# Ref-Board-1_5-WA-r1_0.net
KiCad netlist of a schematic drawn in Altium Designer
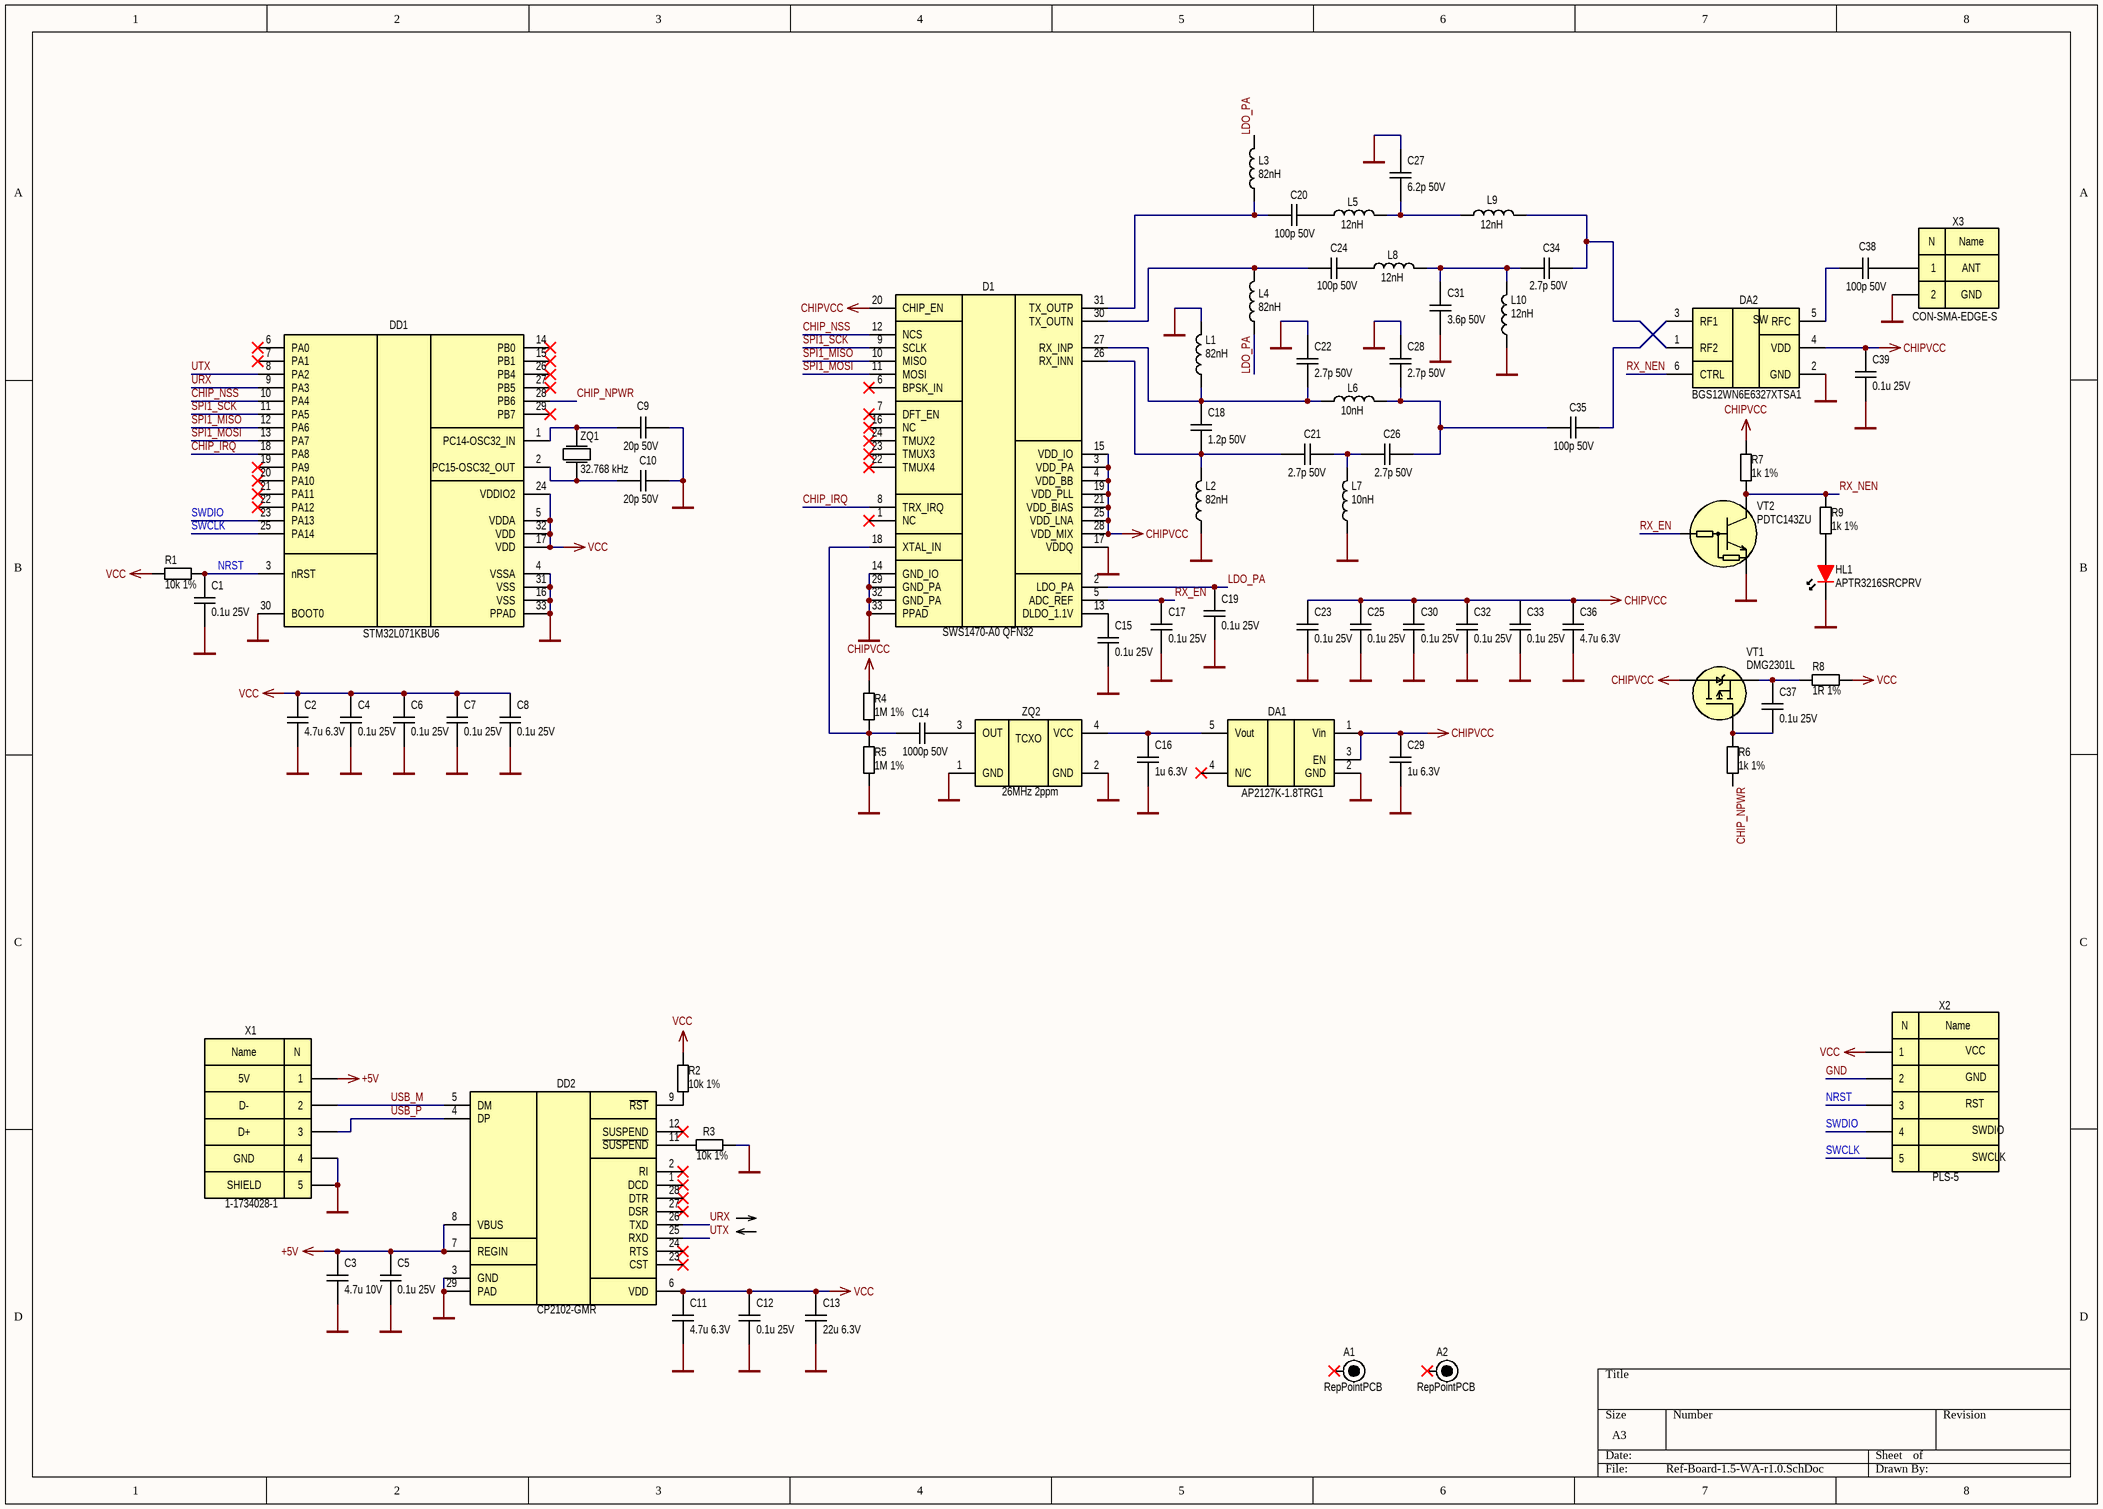
[diagram p0: Ref-Board-1.5-WA-r1.0.SchDoc]

(export (version "E")
  (design (tool "Eeschema 10.0.6"))
  (components
    (comp (ref "A1")
      (value "RepPointPCB")
      (footprint "REPzn")
      (description "Repere point d=0.5mm, D=1mm")
      (libsource (lib "Special") (part "RepPointCircD1.0"))
    )
    (comp (ref "A2")
      (value "RepPointPCB")
      (footprint "REPzn")
      (description "Repere point d=0.5mm, D=1mm")
      (libsource (lib "Special") (part "RepPointCircD1.0"))
    )
    (comp (ref "C1")
      (value "0.1u 25V")
      (footprint "C0402")
      (description "CAP CER 0.1UF 25V X7R 0402")
      (fields (field (name "PARTNUMBER") "CC0402KRX7R8BB104"))
      (libsource (lib "Capacitors") (part "CC0402KRX7R8BB104"))
    )
    (comp (ref "C2")
      (value "4.7u 6.3V")
      (footprint "C0402")
      (description "CAP CER 4.7UF 6.3V X5R 0402")
      (fields (field (name "PARTNUMBER") "CC0402KRX5R5BB475"))
      (libsource (lib "Capacitors") (part "CC0402KRX5R5BB475"))
    )
    (comp (ref "C3")
      (value "4.7u 10V")
      (footprint "C0603")
      (description "CERCAP 4.7/10V 0603 KX5R")
      (fields (field (name "PARTNUMBER") "CC0603KRX5R6BB475"))
      (libsource (lib "Capacitors") (part "CC0603KRX5R6BB475"))
    )
    (comp (ref "C4")
      (value "0.1u 25V")
      (footprint "C0402")
      (description "CAP CER 0.1UF 25V X7R 0402")
      (fields (field (name "PARTNUMBER") "CC0402KRX7R8BB104"))
      (libsource (lib "Capacitors") (part "CC0402KRX7R8BB104"))
    )
    (comp (ref "C5")
      (value "0.1u 25V")
      (footprint "C0402")
      (description "CAP CER 0.1UF 25V X7R 0402")
      (fields (field (name "PARTNUMBER") "CC0402KRX7R8BB104"))
      (libsource (lib "Capacitors") (part "CC0402KRX7R8BB104"))
    )
    (comp (ref "C6")
      (value "0.1u 25V")
      (footprint "C0402")
      (description "CAP CER 0.1UF 25V X7R 0402")
      (fields (field (name "PARTNUMBER") "CC0402KRX7R8BB104"))
      (libsource (lib "Capacitors") (part "CC0402KRX7R8BB104"))
    )
    (comp (ref "C7")
      (value "0.1u 25V")
      (footprint "C0402")
      (description "CAP CER 0.1UF 25V X7R 0402")
      (fields (field (name "PARTNUMBER") "CC0402KRX7R8BB104"))
      (libsource (lib "Capacitors") (part "CC0402KRX7R8BB104"))
    )
    (comp (ref "C8")
      (value "0.1u 25V")
      (footprint "C0402")
      (description "CAP CER 0.1UF 25V X7R 0402")
      (fields (field (name "PARTNUMBER") "CC0402KRX7R8BB104"))
      (libsource (lib "Capacitors") (part "CC0402KRX7R8BB104"))
    )
    (comp (ref "C9")
      (value "20p 50V")
      (footprint "C0402")
      (description "CAP CER 20PF 50V C0G/NPO 0402")
      (fields (field (name "PARTNUMBER") "CC0402JRNPO9BN200"))
      (libsource (lib "Capacitors") (part "CC0402JRNPO9BN200"))
    )
    (comp (ref "C10")
      (value "20p 50V")
      (footprint "C0402")
      (description "CAP CER 20PF 50V C0G/NPO 0402")
      (fields (field (name "PARTNUMBER") "CC0402JRNPO9BN200"))
      (libsource (lib "Capacitors") (part "CC0402JRNPO9BN200"))
    )
    (comp (ref "C11")
      (value "4.7u 6.3V")
      (footprint "C0402")
      (description "CAP CER 4.7UF 6.3V X5R 0402")
      (fields (field (name "PARTNUMBER") "CC0402KRX5R5BB475"))
      (libsource (lib "Capacitors") (part "CC0402KRX5R5BB475"))
    )
    (comp (ref "C12")
      (value "0.1u 25V")
      (footprint "C0402")
      (description "CAP CER 0.1UF 25V X7R 0402")
      (fields (field (name "PARTNUMBER") "CC0402KRX7R8BB104"))
      (libsource (lib "Capacitors") (part "CC0402KRX7R8BB104"))
    )
    (comp (ref "C13")
      (value "22u 6.3V")
      (footprint "C0603")
      (description "CAP CER 22UF 6.3V X5R 0603")
      (fields (field (name "PARTNUMBER") "GRM188R60J226MEA0J"))
      (libsource (lib "Capacitors") (part "GRM188R60J226MEA0J"))
    )
    (comp (ref "C14")
      (value "1000p 50V")
      (footprint "C0402")
      (description "CAP CER 1000PF 50V X7R 0402")
      (fields (field (name "PARTNUMBER") "CC0402JRX7R9BB102"))
      (libsource (lib "Capacitors") (part "CC0402JRX7R9BB102"))
    )
    (comp (ref "C15")
      (value "0.1u 25V")
      (footprint "C0402")
      (description "CAP CER 0.1UF 25V X7R 0402")
      (fields (field (name "PARTNUMBER") "CC0402KRX7R8BB104"))
      (libsource (lib "Capacitors") (part "CC0402KRX7R8BB104"))
    )
    (comp (ref "C16")
      (value "1u 6.3V")
      (footprint "C0402")
      (description "CAP CER 1UF 6.3V X5R 0402")
      (fields (field (name "PARTNUMBER") "CC0402KRX5R5BB105"))
      (libsource (lib "Capacitors") (part "CC0402KRX5R5BB105"))
    )
    (comp (ref "C17")
      (value "0.1u 25V")
      (footprint "C0402")
      (description "CAP CER 0.1UF 25V X7R 0402")
      (fields (field (name "PARTNUMBER") "CC0402KRX7R8BB104"))
      (libsource (lib "Capacitors") (part "CC0402KRX7R8BB104"))
    )
    (comp (ref "C18")
      (value "1.2p 50V")
      (footprint "C0402")
      (description "CAP CER 1.2PF 50V C0G/NPO 0402")
      (fields (field (name "PARTNUMBER") "CC0402BRNPO9BN1R2"))
      (libsource (lib "Capacitors") (part "CC0402BRNPO9BN1R2"))
    )
    (comp (ref "C19")
      (value "0.1u 25V")
      (footprint "C0402")
      (description "CAP CER 0.1UF 25V X7R 0402")
      (fields (field (name "PARTNUMBER") "CC0402KRX7R8BB104"))
      (libsource (lib "Capacitors") (part "CC0402KRX7R8BB104"))
    )
    (comp (ref "C20")
      (value "100p 50V")
      (footprint "C0402")
      (description "CAP CER 100PF 50V C0G/NPO 0402")
      (fields (field (name "PARTNUMBER") "CC0402JRNPO9BN101"))
      (libsource (lib "Capacitors") (part "CC0402JRNPO9BN101"))
    )
    (comp (ref "C21")
      (value "2.7p 50V")
      (footprint "C0402")
      (description "CAP CER 2.7PF 50V C0G/NPO 0402")
      (fields (field (name "PARTNUMBER") "CC0402BRNPO9BN2R7"))
      (libsource (lib "Capacitors") (part "CC0402BRNPO9BN2R7"))
    )
    (comp (ref "C22")
      (value "2.7p 50V")
      (footprint "C0402")
      (description "CAP CER 2.7PF 50V C0G/NPO 0402")
      (fields (field (name "PARTNUMBER") "CC0402BRNPO9BN2R7"))
      (libsource (lib "Capacitors") (part "CC0402BRNPO9BN2R7"))
    )
    (comp (ref "C23")
      (value "0.1u 25V")
      (footprint "C0402")
      (description "CAP CER 0.1UF 25V X7R 0402")
      (fields (field (name "PARTNUMBER") "CC0402KRX7R8BB104"))
      (libsource (lib "Capacitors") (part "CC0402KRX7R8BB104"))
    )
    (comp (ref "C24")
      (value "100p 50V")
      (footprint "C0402")
      (description "CAP CER 100PF 50V C0G/NPO 0402")
      (fields (field (name "PARTNUMBER") "CC0402JRNPO9BN101"))
      (libsource (lib "Capacitors") (part "CC0402JRNPO9BN101"))
    )
    (comp (ref "C25")
      (value "0.1u 25V")
      (footprint "C0402")
      (description "CAP CER 0.1UF 25V X7R 0402")
      (fields (field (name "PARTNUMBER") "CC0402KRX7R8BB104"))
      (libsource (lib "Capacitors") (part "CC0402KRX7R8BB104"))
    )
    (comp (ref "C26")
      (value "2.7p 50V")
      (footprint "C0402")
      (description "CAP CER 2.7PF 50V C0G/NPO 0402")
      (fields (field (name "PARTNUMBER") "CC0402BRNPO9BN2R7"))
      (libsource (lib "Capacitors") (part "CC0402BRNPO9BN2R7"))
    )
    (comp (ref "C27")
      (value "6.2p 50V")
      (footprint "C0402")
      (description "CAP CER 6.2PF 50V NPO 0402")
      (fields (field (name "PARTNUMBER") "CC0402CRNPO9BN6R2"))
      (libsource (lib "Capacitors") (part "CC0402CRNPO9BN6R2"))
    )
    (comp (ref "C28")
      (value "2.7p 50V")
      (footprint "C0402")
      (description "CAP CER 2.7PF 50V C0G/NPO 0402")
      (fields (field (name "PARTNUMBER") "CC0402BRNPO9BN2R7"))
      (libsource (lib "Capacitors") (part "CC0402BRNPO9BN2R7"))
    )
    (comp (ref "C29")
      (value "1u 6.3V")
      (footprint "C0402")
      (description "CAP CER 1UF 6.3V X5R 0402")
      (fields (field (name "PARTNUMBER") "CC0402KRX5R5BB105"))
      (libsource (lib "Capacitors") (part "CC0402KRX5R5BB105"))
    )
    (comp (ref "C30")
      (value "0.1u 25V")
      (footprint "C0402")
      (description "CAP CER 0.1UF 25V X7R 0402")
      (fields (field (name "PARTNUMBER") "CC0402KRX7R8BB104"))
      (libsource (lib "Capacitors") (part "CC0402KRX7R8BB104"))
    )
    (comp (ref "C31")
      (value "3.6p 50V")
      (footprint "C0402")
      (description "CAP CER 3.6PF 50V NPO 0402")
      (fields (field (name "PARTNUMBER") "CC0402BRNPO9BN3R6"))
      (libsource (lib "Capacitors") (part "CC0402BRNPO9BN3R6"))
    )
    (comp (ref "C32")
      (value "0.1u 25V")
      (footprint "C0402")
      (description "CAP CER 0.1UF 25V X7R 0402")
      (fields (field (name "PARTNUMBER") "CC0402KRX7R8BB104"))
      (libsource (lib "Capacitors") (part "CC0402KRX7R8BB104"))
    )
    (comp (ref "C33")
      (value "0.1u 25V")
      (footprint "C0402")
      (description "CAP CER 0.1UF 25V X7R 0402")
      (fields (field (name "PARTNUMBER") "CC0402KRX7R8BB104"))
      (libsource (lib "Capacitors") (part "CC0402KRX7R8BB104"))
    )
    (comp (ref "C34")
      (value "2.7p 50V")
      (footprint "C0402")
      (description "CAP CER 2.7PF 50V C0G/NPO 0402")
      (fields (field (name "PARTNUMBER") "CC0402BRNPO9BN2R7"))
      (libsource (lib "Capacitors") (part "CC0402BRNPO9BN2R7"))
    )
    (comp (ref "C35")
      (value "100p 50V")
      (footprint "C0402")
      (description "CAP CER 100PF 50V C0G/NPO 0402")
      (fields (field (name "PARTNUMBER") "CC0402JRNPO9BN101"))
      (libsource (lib "Capacitors") (part "CC0402JRNPO9BN101"))
    )
    (comp (ref "C36")
      (value "4.7u 6.3V")
      (footprint "C0402")
      (description "CAP CER 4.7UF 6.3V X5R 0402")
      (fields (field (name "PARTNUMBER") "CC0402KRX5R5BB475"))
      (libsource (lib "Capacitors") (part "CC0402KRX5R5BB475"))
    )
    (comp (ref "C37")
      (value "0.1u 25V")
      (footprint "C0402")
      (description "CAP CER 0.1UF 25V X7R 0402")
      (fields (field (name "PARTNUMBER") "CC0402KRX7R8BB104"))
      (libsource (lib "Capacitors") (part "CC0402KRX7R8BB104"))
    )
    (comp (ref "C38")
      (value "100p 50V")
      (footprint "C0402")
      (description "CAP CER 100PF 50V C0G/NPO 0402")
      (fields (field (name "PARTNUMBER") "CC0402JRNPO9BN101"))
      (libsource (lib "Capacitors") (part "CC0402JRNPO9BN101"))
    )
    (comp (ref "C39")
      (value "0.1u 25V")
      (footprint "C0402")
      (description "CAP CER 0.1UF 25V X7R 0402")
      (fields (field (name "PARTNUMBER") "CC0402KRX7R8BB104"))
      (libsource (lib "Capacitors") (part "CC0402KRX7R8BB104"))
    )
    (comp (ref "D1")
      (value "SWS1470-A0 QFN32")
      (footprint "QFN32")
      (description "Waviot NB-Fi RF Transceiver QFN32")
      (libsource (lib "Integrated Circuits (ICs)") (part "SWS1470-A0 QFN32"))
    )
    (comp (ref "DA1")
      (value "AP2127K-1.8TRG1")
      (footprint "SOT23-5")
      (description "LDO Voltage Regulators 1.8V 80mA CMOS LDO w/Enable")
      (libsource (lib "Integrated Circuits (ICs)") (part "AP2127K-1.8TRG1"))
    )
    (comp (ref "DA2")
      (value "BGS12WN6E6327XTSA1")
      (footprint "6-XFDFN")
      (description "RF Switch IC WLAN SPDT 50Ohm PG-TSNP-6-10")
      (libsource (lib "RF, IF and RFID") (part "BGS12WN6E6327XTSA1"))
    )
    (comp (ref "DD1")
      (value "STM32L071KBU6")
      (footprint "UFQFPN32")
      (description "ARM® Cortex®-M0+ STM32L0 Microcontroller IC 32-Bit 32MHz 128KB (128K x 8) FLASH 32-UFQFPN (5x5)")
      (libsource (lib "Integrated Circuits (ICs)") (part "STM32L071KBU6"))
    )
    (comp (ref "DD2")
      (value "CP2102-GMR")
      (footprint "QFN28")
      (description "IC USB-TO-UART BRIDGE 28VQFN")
      (libsource (lib "Integrated Circuits (ICs)") (part "CP2102-GMR"))
    )
    (comp (ref "HL1")
      (value "APTR3216SRCPRV")
      (footprint "LED1206_RED")
      (description "Red 640nm LED Indication - Discrete 1.85V 1206")
      (libsource (lib "Optoelectronics") (part "APTR3216SRCPRV"))
    )
    (comp (ref "L1")
      (value "82nH")
      (footprint "L0402_LQW")
      (description "FIXED IND 82NH 130MA 2.24 OHM")
      (fields (field (name "PARTNUMBER") "LQW15AN82NG00D"))
      (libsource (lib "Inductors, Coils, Chokes") (part "LQW15AN82NG00D"))
    )
    (comp (ref "L2")
      (value "82nH")
      (footprint "L0402_LQW")
      (description "FIXED IND 82NH 130MA 2.24 OHM")
      (fields (field (name "PARTNUMBER") "LQW15AN82NG00D"))
      (libsource (lib "Inductors, Coils, Chokes") (part "LQW15AN82NG00D"))
    )
    (comp (ref "L3")
      (value "82nH")
      (footprint "L0402_LQW")
      (description "FIXED IND 82NH 130MA 2.24 OHM")
      (fields (field (name "PARTNUMBER") "LQW15AN82NG00D"))
      (libsource (lib "Inductors, Coils, Chokes") (part "LQW15AN82NG00D"))
    )
    (comp (ref "L4")
      (value "82nH")
      (footprint "L0402_LQW")
      (description "FIXED IND 82NH 130MA 2.24 OHM")
      (fields (field (name "PARTNUMBER") "LQW15AN82NG00D"))
      (libsource (lib "Inductors, Coils, Chokes") (part "LQW15AN82NG00D"))
    )
    (comp (ref "L5")
      (value "12nH")
      (footprint "L0402_LQW")
      (description "FIXED IND 12NH 500MA 140 MOHM")
      (fields (field (name "PARTNUMBER") "LQW15AN12NG00D"))
      (libsource (lib "Inductors, Coils, Chokes") (part "LQW15AN12NG00D"))
    )
    (comp (ref "L6")
      (value "10nH")
      (footprint "L0402_LQW")
      (description "FIXED IND 10NH 500MA 170 MOHM")
      (fields (field (name "PARTNUMBER") "LQW15AN10NG00D"))
      (libsource (lib "Inductors, Coils, Chokes") (part "LQW15AN10NG00D"))
    )
    (comp (ref "L7")
      (value "10nH")
      (footprint "L0402_LQW")
      (description "FIXED IND 10NH 500MA 170 MOHM")
      (fields (field (name "PARTNUMBER") "LQW15AN10NG00D"))
      (libsource (lib "Inductors, Coils, Chokes") (part "LQW15AN10NG00D"))
    )
    (comp (ref "L8")
      (value "12nH")
      (footprint "L0402_LQW")
      (description "FIXED IND 12NH 500MA 140 MOHM")
      (fields (field (name "PARTNUMBER") "LQW15AN12NG00D"))
      (libsource (lib "Inductors, Coils, Chokes") (part "LQW15AN12NG00D"))
    )
    (comp (ref "L9")
      (value "12nH")
      (footprint "L0402_LQW")
      (description "FIXED IND 12NH 500MA 140 MOHM")
      (fields (field (name "PARTNUMBER") "LQW15AN12NG00D"))
      (libsource (lib "Inductors, Coils, Chokes") (part "LQW15AN12NG00D"))
    )
    (comp (ref "L10")
      (value "12nH")
      (footprint "L0402_LQW")
      (description "FIXED IND 12NH 500MA 140 MOHM")
      (fields (field (name "PARTNUMBER") "LQW15AN12NG00D"))
      (libsource (lib "Inductors, Coils, Chokes") (part "LQW15AN12NG00D"))
    )
    (comp (ref "R1")
      (value "10k 1%")
      (footprint "R0402")
      (description "RES SMD 10K OHM 1% 1/16W 0402")
      (fields (field (name "PARTNUMBER") "RC0402FR-0710KL"))
      (libsource (lib "Resistors") (part "RC0402FR-0710KL"))
    )
    (comp (ref "R2")
      (value "10k 1%")
      (footprint "R0402")
      (description "RES SMD 10K OHM 1% 1/16W 0402")
      (fields (field (name "PARTNUMBER") "RC0402FR-0710KL"))
      (libsource (lib "Resistors") (part "RC0402FR-0710KL"))
    )
    (comp (ref "R3")
      (value "10k 1%")
      (footprint "R0402")
      (description "RES SMD 10K OHM 1% 1/16W 0402")
      (fields (field (name "PARTNUMBER") "RC0402FR-0710KL"))
      (libsource (lib "") (part "RC0402FR-0710KL_1"))
    )
    (comp (ref "R4")
      (value "1M 1%")
      (footprint "R0402")
      (description "RES SMD 1M OHM 1% 1/16W 0402")
      (fields (field (name "PARTNUMBER") "RC0402FR-071ML"))
      (libsource (lib "Resistors") (part "RC0402FR-071ML"))
    )
    (comp (ref "R5")
      (value "1M 1%")
      (footprint "R0402")
      (description "RES SMD 1M OHM 1% 1/16W 0402")
      (fields (field (name "PARTNUMBER") "RC0402FR-071ML"))
      (libsource (lib "Resistors") (part "RC0402FR-071ML"))
    )
    (comp (ref "R6")
      (value "1k 1%")
      (footprint "R0402")
      (description "RES SMD 1K OHM 1% 1/16W 0402")
      (fields (field (name "PARTNUMBER") "RC0402FR-071KL"))
      (libsource (lib "") (part "RC0402FR-071KL_1"))
    )
    (comp (ref "R7")
      (value "1k 1%")
      (footprint "R0402")
      (description "RES SMD 1K OHM 1% 1/16W 0402")
      (fields (field (name "PARTNUMBER") "RC0402FR-071KL"))
      (libsource (lib "Resistors") (part "RC0402FR-071KL"))
    )
    (comp (ref "R8")
      (value "1R 1%")
      (footprint "R0402")
      (description "RES SMD 1 OHM 1% 1/16W 0402")
      (fields (field (name "PARTNUMBER") "RC0402FR-071RL"))
      (libsource (lib "Resistors") (part "RC0402FR-071RL"))
    )
    (comp (ref "R9")
      (value "1k 1%")
      (footprint "R0402")
      (description "RES SMD 1K OHM 1% 1/16W 0402")
      (fields (field (name "PARTNUMBER") "RC0402FR-071KL"))
      (libsource (lib "Resistors") (part "RC0402FR-071KL"))
    )
    (comp (ref "VT1")
      (value "DMG2301L")
      (footprint "SOT23-3L")
      (description "MOSFET P-CH 20V 3A SOT23")
      (libsource (lib "Discrete Semiconductor Products") (part "DMG2301L"))
    )
    (comp (ref "VT2")
      (value "PDTC143ZU")
      (footprint "SOT323")
      (description "TRANS PREBIAS NPN 200MW SOT323")
      (libsource (lib "Discrete Semiconductor Products") (part "PDTC143ZU"))
    )
    (comp (ref "X1")
      (value "1-1734028-1")
      (footprint "1-1734028-1")
      (description "USB-A (USB TYPE-A) USB 2.0 Plug")
      (libsource (lib "Connectors") (part "1-1734028-1"))
    )
    (comp (ref "X2")
      (value "PLS-5")
      (footprint "PLS-5-2.54-PCB")
      (description "PLS-5-2.54")
      (libsource (lib "Connectors") (part "PLS-5"))
    )
    (comp (ref "X3")
      (value "CON-SMA-EDGE-S")
      (footprint "CON-SMA-EDGE-S")
      (description "CONN SMA JACK STR EDGE MNT")
      (libsource (lib "Connectors") (part "CON-SMA-EDGE-S"))
    )
    (comp (ref "ZQ1")
      (value "32.768 kHz")
      (footprint "QSMD3.2X1.5X0.8")
      (description "CRYSTAL 32.768KHZ 12.5PF SMD")
      (fields (field (name "PARTNUMBER") "NX3215SA-32.768K-EXS00A"))
      (libsource (lib "Crystals, Oscillators, Resonators") (part "NX3215SA-32.768K-EXS00A"))
    )
    (comp (ref "ZQ2")
      (value "26MHz 2ppm")
      (footprint "QSMD2.0x1.6x0.7")
      (description "TCXO Oscillator 4-pin")
      (fields (field (name "PARTNUMBER") "NT2016SA-26.000000MHZ-NBG2"))
      (libsource (lib "Crystals, Oscillators, Resonators") (part "NT2016SA-26.000000MHZ-NBG2"))
    )
  )
  (nets
    (net (code "1") (name "+5V") (class "Default")
      (node (ref "C3") (pin "2") (pinfunction "2_2") (pintype "passive"))
      (node (ref "C5") (pin "2") (pinfunction "2_2") (pintype "passive"))
      (node (ref "DD2") (pin "7") (pinfunction "REGIN_7") (pintype "passive"))
      (node (ref "DD2") (pin "8") (pinfunction "VBUS_8") (pintype "passive"))
      (node (ref "X1") (pin "1") (pinfunction "1_1") (pintype "passive"))
    )
    (net (code "2") (name "/CHIP_IRQ") (class "Default")
      (node (ref "D1") (pin "8") (pinfunction "TRX_IRQ_8") (pintype "passive"))
      (node (ref "DD1") (pin "18") (pinfunction "PA8_18") (pintype "passive"))
    )
    (net (code "3") (name "/CHIP_NPWR") (class "Default")
      (node (ref "DD1") (pin "28") (pinfunction "PB6_28") (pintype "passive"))
      (node (ref "R6") (pin "1") (pinfunction "1_1") (pintype "passive"))
    )
    (net (code "4") (name "/CHIP_NSS") (class "Default")
      (node (ref "D1") (pin "12") (pinfunction "NCS_12") (pintype "passive"))
      (node (ref "DD1") (pin "10") (pinfunction "PA4_10") (pintype "passive"))
    )
    (net (code "5") (name "/LDO_PA") (class "Default")
      (node (ref "C19") (pin "2") (pinfunction "2_2") (pintype "passive"))
      (node (ref "D1") (pin "2") (pinfunction "LDO_PA_2") (pintype "passive"))
      (node (ref "L3") (pin "2") (pinfunction "2_2") (pintype "passive"))
      (node (ref "L4") (pin "1") (pinfunction "1_1") (pintype "passive"))
    )
    (net (code "6") (name "/NRST") (class "Default")
      (node (ref "C1") (pin "1") (pinfunction "1_1") (pintype "passive"))
      (node (ref "DD1") (pin "3") (pinfunction "nRST_3") (pintype "passive"))
      (node (ref "R1") (pin "2") (pinfunction "2_2") (pintype "passive"))
      (node (ref "X2") (pin "3") (pinfunction "3_3") (pintype "passive"))
    )
    (net (code "7") (name "/RX_EN") (class "Default")
      (node (ref "C17") (pin "2") (pinfunction "2_2") (pintype "passive"))
      (node (ref "D1") (pin "5") (pinfunction "ADC_REF_5") (pintype "passive"))
      (node (ref "VT2") (pin "1") (pinfunction "1_1") (pintype "passive"))
    )
    (net (code "8") (name "/RX_NEN") (class "Default")
      (node (ref "DA2") (pin "6") (pinfunction "CTRL_6") (pintype "passive"))
      (node (ref "R7") (pin "2") (pinfunction "2_2") (pintype "passive"))
      (node (ref "R9") (pin "1") (pinfunction "1_1") (pintype "passive"))
      (node (ref "VT2") (pin "3") (pinfunction "3_3") (pintype "passive"))
    )
    (net (code "9") (name "/SPI1_MISO") (class "Default")
      (node (ref "D1") (pin "10") (pinfunction "MISO_10") (pintype "passive"))
      (node (ref "DD1") (pin "12") (pinfunction "PA6_12") (pintype "passive"))
    )
    (net (code "10") (name "/SPI1_MOSI") (class "Default")
      (node (ref "D1") (pin "11") (pinfunction "MOSI_11") (pintype "passive"))
      (node (ref "DD1") (pin "13") (pinfunction "PA7_13") (pintype "passive"))
    )
    (net (code "11") (name "/SPI1_SCK") (class "Default")
      (node (ref "D1") (pin "9") (pinfunction "SCLK_9") (pintype "passive"))
      (node (ref "DD1") (pin "11") (pinfunction "PA5_11") (pintype "passive"))
    )
    (net (code "12") (name "/SWCLK") (class "Default")
      (node (ref "DD1") (pin "25") (pinfunction "PA14_25") (pintype "passive"))
      (node (ref "X2") (pin "5") (pinfunction "5_5") (pintype "passive"))
    )
    (net (code "13") (name "/SWDIO") (class "Default")
      (node (ref "DD1") (pin "23") (pinfunction "PA13_23") (pintype "passive"))
      (node (ref "X2") (pin "4") (pinfunction "4_4") (pintype "passive"))
    )
    (net (code "14") (name "/URX") (class "Default")
      (node (ref "DD1") (pin "9") (pinfunction "PA3_9") (pintype "passive"))
      (node (ref "DD2") (pin "26") (pinfunction "TXD_26") (pintype "passive"))
    )
    (net (code "15") (name "/USB_M") (class "Default")
      (node (ref "DD2") (pin "5") (pinfunction "DM_5") (pintype "passive"))
      (node (ref "X1") (pin "2") (pinfunction "2_2") (pintype "passive"))
    )
    (net (code "16") (name "/USB_P") (class "Default")
      (node (ref "DD2") (pin "4") (pinfunction "DP_4") (pintype "passive"))
      (node (ref "X1") (pin "3") (pinfunction "3_3") (pintype "passive"))
    )
    (net (code "17") (name "/UTX") (class "Default")
      (node (ref "DD1") (pin "8") (pinfunction "PA2_8") (pintype "passive"))
      (node (ref "DD2") (pin "25") (pinfunction "RXD_25") (pintype "passive"))
    )
    (net (code "18") (name "CHIPVCC") (class "Default")
      (node (ref "C23") (pin "2") (pinfunction "2_2") (pintype "passive"))
      (node (ref "C25") (pin "2") (pinfunction "2_2") (pintype "passive"))
      (node (ref "C29") (pin "2") (pinfunction "2_2") (pintype "passive"))
      (node (ref "C30") (pin "2") (pinfunction "2_2") (pintype "passive"))
      (node (ref "C32") (pin "2") (pinfunction "2_2") (pintype "passive"))
      (node (ref "C33") (pin "2") (pinfunction "2_2") (pintype "passive"))
      (node (ref "C36") (pin "2") (pinfunction "2_2") (pintype "passive"))
      (node (ref "C39") (pin "2") (pinfunction "2_2") (pintype "passive"))
      (node (ref "D1") (pin "15") (pinfunction "VDD_IO_15") (pintype "passive"))
      (node (ref "D1") (pin "19") (pinfunction "VDD_PLL_19") (pintype "passive"))
      (node (ref "D1") (pin "20") (pinfunction "CHIP_EN_20") (pintype "passive"))
      (node (ref "D1") (pin "21") (pinfunction "VDD_BIAS_21") (pintype "passive"))
      (node (ref "D1") (pin "25") (pinfunction "VDD_LNA_25") (pintype "passive"))
      (node (ref "D1") (pin "28") (pinfunction "VDD_MIX_28") (pintype "passive"))
      (node (ref "D1") (pin "3") (pinfunction "VDD_PA_3") (pintype "passive"))
      (node (ref "D1") (pin "4") (pinfunction "VDD_BB_4") (pintype "passive"))
      (node (ref "DA1") (pin "1") (pinfunction "Vin_1") (pintype "passive"))
      (node (ref "DA1") (pin "3") (pinfunction "EN_3") (pintype "passive"))
      (node (ref "DA2") (pin "4") (pinfunction "VDD_4") (pintype "passive"))
      (node (ref "R4") (pin "2") (pinfunction "2_2") (pintype "passive"))
      (node (ref "R7") (pin "1") (pinfunction "1_1") (pintype "passive"))
      (node (ref "VT1") (pin "3") (pinfunction "D_3") (pintype "passive"))
    )
    (net (code "19") (name "GND") (class "Default")
      (node (ref "C1") (pin "2") (pinfunction "2_2") (pintype "passive"))
      (node (ref "C10") (pin "2") (pinfunction "2_2") (pintype "passive"))
      (node (ref "C11") (pin "1") (pinfunction "1_1") (pintype "passive"))
      (node (ref "C12") (pin "1") (pinfunction "1_1") (pintype "passive"))
      (node (ref "C13") (pin "1") (pinfunction "1_1") (pintype "passive"))
      (node (ref "C15") (pin "1") (pinfunction "1_1") (pintype "passive"))
      (node (ref "C16") (pin "1") (pinfunction "1_1") (pintype "passive"))
      (node (ref "C17") (pin "1") (pinfunction "1_1") (pintype "passive"))
      (node (ref "C19") (pin "1") (pinfunction "1_1") (pintype "passive"))
      (node (ref "C2") (pin "2") (pinfunction "2_2") (pintype "passive"))
      (node (ref "C22") (pin "1") (pinfunction "1_1") (pintype "passive"))
      (node (ref "C23") (pin "1") (pinfunction "1_1") (pintype "passive"))
      (node (ref "C25") (pin "1") (pinfunction "1_1") (pintype "passive"))
      (node (ref "C27") (pin "1") (pinfunction "1_1") (pintype "passive"))
      (node (ref "C28") (pin "1") (pinfunction "1_1") (pintype "passive"))
      (node (ref "C29") (pin "1") (pinfunction "1_1") (pintype "passive"))
      (node (ref "C3") (pin "1") (pinfunction "1_1") (pintype "passive"))
      (node (ref "C30") (pin "1") (pinfunction "1_1") (pintype "passive"))
      (node (ref "C31") (pin "2") (pinfunction "2_2") (pintype "passive"))
      (node (ref "C32") (pin "1") (pinfunction "1_1") (pintype "passive"))
      (node (ref "C33") (pin "1") (pinfunction "1_1") (pintype "passive"))
      (node (ref "C36") (pin "1") (pinfunction "1_1") (pintype "passive"))
      (node (ref "C39") (pin "1") (pinfunction "1_1") (pintype "passive"))
      (node (ref "C4") (pin "2") (pinfunction "2_2") (pintype "passive"))
      (node (ref "C5") (pin "1") (pinfunction "1_1") (pintype "passive"))
      (node (ref "C6") (pin "2") (pinfunction "2_2") (pintype "passive"))
      (node (ref "C7") (pin "2") (pinfunction "2_2") (pintype "passive"))
      (node (ref "C8") (pin "2") (pinfunction "2_2") (pintype "passive"))
      (node (ref "C9") (pin "2") (pinfunction "2_2") (pintype "passive"))
      (node (ref "D1") (pin "14") (pinfunction "GND_IO_14") (pintype "passive"))
      (node (ref "D1") (pin "17") (pinfunction "VDDQ_17") (pintype "passive"))
      (node (ref "D1") (pin "29") (pinfunction "GND_PA_29") (pintype "passive"))
      (node (ref "D1") (pin "32") (pinfunction "GND_PA_32") (pintype "passive"))
      (node (ref "D1") (pin "33") (pinfunction "PPAD_33") (pintype "passive"))
      (node (ref "DA1") (pin "2") (pinfunction "GND_2") (pintype "passive"))
      (node (ref "DA2") (pin "2") (pinfunction "GND_2") (pintype "passive"))
      (node (ref "DD1") (pin "16") (pinfunction "VSS_16") (pintype "power_in"))
      (node (ref "DD1") (pin "30") (pinfunction "BOOT0_30") (pintype "passive"))
      (node (ref "DD1") (pin "31") (pinfunction "VSS_31") (pintype "power_in"))
      (node (ref "DD1") (pin "33") (pinfunction "PPAD_33") (pintype "power_in"))
      (node (ref "DD1") (pin "4") (pinfunction "VSSA_4") (pintype "power_in"))
      (node (ref "DD2") (pin "29") (pinfunction "PAD_29") (pintype "passive"))
      (node (ref "DD2") (pin "3") (pinfunction "GND_3") (pintype "passive"))
      (node (ref "HL1") (pin "2") (pinfunction "2_2") (pintype "passive"))
      (node (ref "L1") (pin "2") (pinfunction "2_2") (pintype "passive"))
      (node (ref "L10") (pin "1") (pinfunction "1_1") (pintype "passive"))
      (node (ref "L2") (pin "1") (pinfunction "1_1") (pintype "passive"))
      (node (ref "L7") (pin "1") (pinfunction "1_1") (pintype "passive"))
      (node (ref "R3") (pin "1") (pinfunction "1_1") (pintype "passive"))
      (node (ref "R5") (pin "1") (pinfunction "1_1") (pintype "passive"))
      (node (ref "VT2") (pin "2") (pinfunction "2_2") (pintype "passive"))
      (node (ref "X1") (pin "4") (pinfunction "4_4") (pintype "passive"))
      (node (ref "X1") (pin "5") (pinfunction "5_5") (pintype "passive"))
      (node (ref "X2") (pin "2") (pinfunction "2_2") (pintype "passive"))
      (node (ref "X3") (pin "2") (pinfunction "2_2") (pintype "passive"))
      (node (ref "ZQ2") (pin "1") (pinfunction "GND_1") (pintype "passive"))
      (node (ref "ZQ2") (pin "2") (pinfunction "GND_2") (pintype "passive"))
    )
    (net (code "20") (name "Net-(C20-Pad2)") (class "Default")
      (node (ref "C20") (pin "2") (pinfunction "2_2") (pintype "passive"))
      (node (ref "L5") (pin "1") (pinfunction "1_1") (pintype "passive"))
    )
    (net (code "21") (name "Net-(C21-Pad2)") (class "Default")
      (node (ref "C21") (pin "2") (pinfunction "2_2") (pintype "passive"))
      (node (ref "C26") (pin "1") (pinfunction "1_1") (pintype "passive"))
      (node (ref "L7") (pin "2") (pinfunction "2_2") (pintype "passive"))
    )
    (net (code "22") (name "Net-(C24-Pad2)") (class "Default")
      (node (ref "C24") (pin "2") (pinfunction "2_2") (pintype "passive"))
      (node (ref "L8") (pin "1") (pinfunction "1_1") (pintype "passive"))
    )
    (net (code "23") (name "Net-(C26-Pad2)") (class "Default")
      (node (ref "C26") (pin "2") (pinfunction "2_2") (pintype "passive"))
      (node (ref "C28") (pin "2") (pinfunction "2_2") (pintype "passive"))
      (node (ref "C35") (pin "1") (pinfunction "1_1") (pintype "passive"))
      (node (ref "L6") (pin "2") (pinfunction "2_2") (pintype "passive"))
    )
    (net (code "24") (name "Net-(C27-Pad2)") (class "Default")
      (node (ref "C27") (pin "2") (pinfunction "2_2") (pintype "passive"))
      (node (ref "L5") (pin "2") (pinfunction "2_2") (pintype "passive"))
      (node (ref "L9") (pin "1") (pinfunction "1_1") (pintype "passive"))
    )
    (net (code "25") (name "Net-(C31-Pad1)") (class "Default")
      (node (ref "C31") (pin "1") (pinfunction "1_1") (pintype "passive"))
      (node (ref "C34") (pin "1") (pinfunction "1_1") (pintype "passive"))
      (node (ref "L10") (pin "2") (pinfunction "2_2") (pintype "passive"))
      (node (ref "L8") (pin "2") (pinfunction "2_2") (pintype "passive"))
    )
    (net (code "26") (name "Net-(C38-Pad2)") (class "Default")
      (node (ref "C38") (pin "2") (pinfunction "2_2") (pintype "passive"))
      (node (ref "X3") (pin "1") (pinfunction "1_1") (pintype "passive"))
    )
    (net (code "27") (name "Net-(D1-DLDO_1.1V)") (class "Default")
      (node (ref "C15") (pin "2") (pinfunction "2_2") (pintype "passive"))
      (node (ref "D1") (pin "13") (pinfunction "DLDO_1.1V_13") (pintype "passive"))
    )
    (net (code "28") (name "Net-(D1-RX_INN)") (class "Default")
      (node (ref "C18") (pin "2") (pinfunction "2_2") (pintype "passive"))
      (node (ref "C21") (pin "1") (pinfunction "1_1") (pintype "passive"))
      (node (ref "D1") (pin "26") (pinfunction "RX_INN_26") (pintype "passive"))
      (node (ref "L2") (pin "2") (pinfunction "2_2") (pintype "passive"))
    )
    (net (code "29") (name "Net-(D1-RX_INP)") (class "Default")
      (node (ref "C18") (pin "1") (pinfunction "1_1") (pintype "passive"))
      (node (ref "C22") (pin "2") (pinfunction "2_2") (pintype "passive"))
      (node (ref "D1") (pin "27") (pinfunction "RX_INP_27") (pintype "passive"))
      (node (ref "L1") (pin "1") (pinfunction "1_1") (pintype "passive"))
      (node (ref "L6") (pin "1") (pinfunction "1_1") (pintype "passive"))
    )
    (net (code "30") (name "Net-(D1-TX_OUTN)") (class "Default")
      (node (ref "C24") (pin "1") (pinfunction "1_1") (pintype "passive"))
      (node (ref "D1") (pin "30") (pinfunction "TX_OUTN_30") (pintype "passive"))
      (node (ref "L4") (pin "2") (pinfunction "2_2") (pintype "passive"))
    )
    (net (code "31") (name "Net-(D1-TX_OUTP)") (class "Default")
      (node (ref "C20") (pin "1") (pinfunction "1_1") (pintype "passive"))
      (node (ref "D1") (pin "31") (pinfunction "TX_OUTP_31") (pintype "passive"))
      (node (ref "L3") (pin "1") (pinfunction "1_1") (pintype "passive"))
    )
    (net (code "32") (name "Net-(D1-XTAL_IN)") (class "Default")
      (node (ref "C14") (pin "2") (pinfunction "2_2") (pintype "passive"))
      (node (ref "D1") (pin "18") (pinfunction "XTAL_IN_18") (pintype "passive"))
      (node (ref "R4") (pin "1") (pinfunction "1_1") (pintype "passive"))
      (node (ref "R5") (pin "2") (pinfunction "2_2") (pintype "passive"))
    )
    (net (code "33") (name "Net-(DA1-Vout)") (class "Default")
      (node (ref "C16") (pin "2") (pinfunction "2_2") (pintype "passive"))
      (node (ref "DA1") (pin "5") (pinfunction "Vout_5") (pintype "passive"))
      (node (ref "ZQ2") (pin "4") (pinfunction "VCC_4") (pintype "passive"))
    )
    (net (code "34") (name "Net-(DA2-RF1)") (class "Default")
      (node (ref "C35") (pin "2") (pinfunction "2_2") (pintype "passive"))
      (node (ref "DA2") (pin "3") (pinfunction "RF1_3") (pintype "passive"))
    )
    (net (code "35") (name "Net-(DA2-RF2)") (class "Default")
      (node (ref "C34") (pin "2") (pinfunction "2_2") (pintype "passive"))
      (node (ref "DA2") (pin "1") (pinfunction "RF2_1") (pintype "passive"))
      (node (ref "L9") (pin "2") (pinfunction "2_2") (pintype "passive"))
    )
    (net (code "36") (name "Net-(DA2-RFC)") (class "Default")
      (node (ref "C38") (pin "1") (pinfunction "1_1") (pintype "passive"))
      (node (ref "DA2") (pin "5") (pinfunction "RFC_5") (pintype "passive"))
    )
    (net (code "37") (name "Net-(DD1-PC14-OSC32_IN)") (class "Default")
      (node (ref "C9") (pin "1") (pinfunction "1_1") (pintype "passive"))
      (node (ref "DD1") (pin "1") (pinfunction "PC14-OSC32_IN_1") (pintype "passive"))
      (node (ref "ZQ1") (pin "1") (pinfunction "1_1") (pintype "passive"))
    )
    (net (code "38") (name "Net-(DD1-PC15-OSC32_OUT)") (class "Default")
      (node (ref "C10") (pin "1") (pinfunction "1_1") (pintype "passive"))
      (node (ref "DD1") (pin "2") (pinfunction "PC15-OSC32_OUT_2") (pintype "passive"))
      (node (ref "ZQ1") (pin "3") (pinfunction "3_3") (pintype "passive"))
    )
    (net (code "39") (name "Net-(DD2-~{RST})") (class "Default")
      (node (ref "DD2") (pin "9") (pinfunction "~{RST}_9") (pintype "passive"))
      (node (ref "R2") (pin "1") (pinfunction "1_1") (pintype "passive"))
    )
    (net (code "40") (name "Net-(DD2-~{SUSPEND})") (class "Default")
      (node (ref "DD2") (pin "11") (pinfunction "~{SUSPEND}_11") (pintype "passive"))
      (node (ref "R3") (pin "2") (pinfunction "2_2") (pintype "passive"))
    )
    (net (code "41") (name "Net-(HL1-Pad1)") (class "Default")
      (node (ref "HL1") (pin "1") (pinfunction "1_1") (pintype "passive"))
      (node (ref "R9") (pin "2") (pinfunction "2_2") (pintype "passive"))
    )
    (net (code "42") (name "Net-(VT1-G)") (class "Default")
      (node (ref "C37") (pin "1") (pinfunction "1_1") (pintype "passive"))
      (node (ref "R6") (pin "2") (pinfunction "2_2") (pintype "passive"))
      (node (ref "VT1") (pin "1") (pinfunction "G_1") (pintype "passive"))
    )
    (net (code "43") (name "Net-(VT1-S)") (class "Default")
      (node (ref "C37") (pin "2") (pinfunction "2_2") (pintype "passive"))
      (node (ref "R8") (pin "2") (pinfunction "2_2") (pintype "passive"))
      (node (ref "VT1") (pin "2") (pinfunction "S_2") (pintype "passive"))
    )
    (net (code "44") (name "Net-(ZQ2-OUT)") (class "Default")
      (node (ref "C14") (pin "1") (pinfunction "1_1") (pintype "passive"))
      (node (ref "ZQ2") (pin "3") (pinfunction "OUT_3") (pintype "passive"))
    )
    (net (code "45") (name "VCC") (class "Default")
      (node (ref "C11") (pin "2") (pinfunction "2_2") (pintype "passive"))
      (node (ref "C12") (pin "2") (pinfunction "2_2") (pintype "passive"))
      (node (ref "C13") (pin "2") (pinfunction "2_2") (pintype "passive"))
      (node (ref "C2") (pin "1") (pinfunction "1_1") (pintype "passive"))
      (node (ref "C4") (pin "1") (pinfunction "1_1") (pintype "passive"))
      (node (ref "C6") (pin "1") (pinfunction "1_1") (pintype "passive"))
      (node (ref "C7") (pin "1") (pinfunction "1_1") (pintype "passive"))
      (node (ref "C8") (pin "1") (pinfunction "1_1") (pintype "passive"))
      (node (ref "DD1") (pin "17") (pinfunction "VDD_17") (pintype "power_in"))
      (node (ref "DD1") (pin "24") (pinfunction "VDDIO2_24") (pintype "power_in"))
      (node (ref "DD1") (pin "32") (pinfunction "VDD_32") (pintype "power_in"))
      (node (ref "DD1") (pin "5") (pinfunction "VDDA_5") (pintype "power_in"))
      (node (ref "DD2") (pin "6") (pinfunction "VDD_6") (pintype "passive"))
      (node (ref "R1") (pin "1") (pinfunction "1_1") (pintype "passive"))
      (node (ref "R2") (pin "2") (pinfunction "2_2") (pintype "passive"))
      (node (ref "R8") (pin "1") (pinfunction "1_1") (pintype "passive"))
      (node (ref "X2") (pin "1") (pinfunction "1_1") (pintype "passive"))
    )
    (net (code "46") (name "unconnected-(A1-Pad1)") (class "Default")
      (node (ref "A1") (pin "1") (pinfunction "1_1") (pintype "passive+no_connect"))
    )
    (net (code "47") (name "unconnected-(A2-Pad1)") (class "Default")
      (node (ref "A2") (pin "1") (pinfunction "1_1") (pintype "passive+no_connect"))
    )
    (net (code "48") (name "unconnected-(D1-BPSK_IN-Pad6)") (class "Default")
      (node (ref "D1") (pin "6") (pinfunction "BPSK_IN_6") (pintype "passive+no_connect"))
    )
    (net (code "49") (name "unconnected-(D1-DFT_EN-Pad7)") (class "Default")
      (node (ref "D1") (pin "7") (pinfunction "DFT_EN_7") (pintype "passive+no_connect"))
    )
    (net (code "50") (name "unconnected-(D1-NC-Pad1)") (class "Default")
      (node (ref "D1") (pin "1") (pinfunction "NC_1") (pintype "passive+no_connect"))
    )
    (net (code "51") (name "unconnected-(D1-NC-Pad16)") (class "Default")
      (node (ref "D1") (pin "16") (pinfunction "NC_16") (pintype "passive+no_connect"))
    )
    (net (code "52") (name "unconnected-(D1-TMUX2-Pad24)") (class "Default")
      (node (ref "D1") (pin "24") (pinfunction "TMUX2_24") (pintype "passive+no_connect"))
    )
    (net (code "53") (name "unconnected-(D1-TMUX3-Pad23)") (class "Default")
      (node (ref "D1") (pin "23") (pinfunction "TMUX3_23") (pintype "passive+no_connect"))
    )
    (net (code "54") (name "unconnected-(D1-TMUX4-Pad22)") (class "Default")
      (node (ref "D1") (pin "22") (pinfunction "TMUX4_22") (pintype "passive+no_connect"))
    )
    (net (code "55") (name "unconnected-(DA1-N{slash}C-Pad4)") (class "Default")
      (node (ref "DA1") (pin "4") (pinfunction "N/C_4") (pintype "passive+no_connect"))
    )
    (net (code "56") (name "unconnected-(DD1-PA0-Pad6)") (class "Default")
      (node (ref "DD1") (pin "6") (pinfunction "PA0_6") (pintype "passive+no_connect"))
    )
    (net (code "57") (name "unconnected-(DD1-PA1-Pad7)") (class "Default")
      (node (ref "DD1") (pin "7") (pinfunction "PA1_7") (pintype "passive+no_connect"))
    )
    (net (code "58") (name "unconnected-(DD1-PA9-Pad19)") (class "Default")
      (node (ref "DD1") (pin "19") (pinfunction "PA9_19") (pintype "passive+no_connect"))
    )
    (net (code "59") (name "unconnected-(DD1-PA10-Pad20)") (class "Default")
      (node (ref "DD1") (pin "20") (pinfunction "PA10_20") (pintype "passive+no_connect"))
    )
    (net (code "60") (name "unconnected-(DD1-PA11-Pad21)") (class "Default")
      (node (ref "DD1") (pin "21") (pinfunction "PA11_21") (pintype "passive+no_connect"))
    )
    (net (code "61") (name "unconnected-(DD1-PA12-Pad22)") (class "Default")
      (node (ref "DD1") (pin "22") (pinfunction "PA12_22") (pintype "passive+no_connect"))
    )
    (net (code "62") (name "unconnected-(DD1-PB0-Pad14)") (class "Default")
      (node (ref "DD1") (pin "14") (pinfunction "PB0_14") (pintype "passive+no_connect"))
    )
    (net (code "63") (name "unconnected-(DD1-PB1-Pad15)") (class "Default")
      (node (ref "DD1") (pin "15") (pinfunction "PB1_15") (pintype "passive+no_connect"))
    )
    (net (code "64") (name "unconnected-(DD1-PB4-Pad26)") (class "Default")
      (node (ref "DD1") (pin "26") (pinfunction "PB4_26") (pintype "passive+no_connect"))
    )
    (net (code "65") (name "unconnected-(DD1-PB5-Pad27)") (class "Default")
      (node (ref "DD1") (pin "27") (pinfunction "PB5_27") (pintype "passive+no_connect"))
    )
    (net (code "66") (name "unconnected-(DD1-PB7-Pad29)") (class "Default")
      (node (ref "DD1") (pin "29") (pinfunction "PB7_29") (pintype "passive+no_connect"))
    )
    (net (code "67") (name "unconnected-(DD2-CST-Pad23)") (class "Default")
      (node (ref "DD2") (pin "23") (pinfunction "CST_23") (pintype "passive+no_connect"))
    )
    (net (code "68") (name "unconnected-(DD2-DCD-Pad1)") (class "Default")
      (node (ref "DD2") (pin "1") (pinfunction "DCD_1") (pintype "passive+no_connect"))
    )
    (net (code "69") (name "unconnected-(DD2-DSR-Pad27)") (class "Default")
      (node (ref "DD2") (pin "27") (pinfunction "DSR_27") (pintype "passive+no_connect"))
    )
    (net (code "70") (name "unconnected-(DD2-DTR-Pad28)") (class "Default")
      (node (ref "DD2") (pin "28") (pinfunction "DTR_28") (pintype "passive+no_connect"))
    )
    (net (code "71") (name "unconnected-(DD2-RI-Pad2)") (class "Default")
      (node (ref "DD2") (pin "2") (pinfunction "RI_2") (pintype "passive+no_connect"))
    )
    (net (code "72") (name "unconnected-(DD2-RTS-Pad24)") (class "Default")
      (node (ref "DD2") (pin "24") (pinfunction "RTS_24") (pintype "passive+no_connect"))
    )
    (net (code "73") (name "unconnected-(DD2-SUSPEND-Pad12)") (class "Default")
      (node (ref "DD2") (pin "12") (pinfunction "SUSPEND_12") (pintype "passive+no_connect"))
    )
  )
)
